# showroom_v1_schematic.net
KiCad netlist of a schematic drawn in Altium Designer
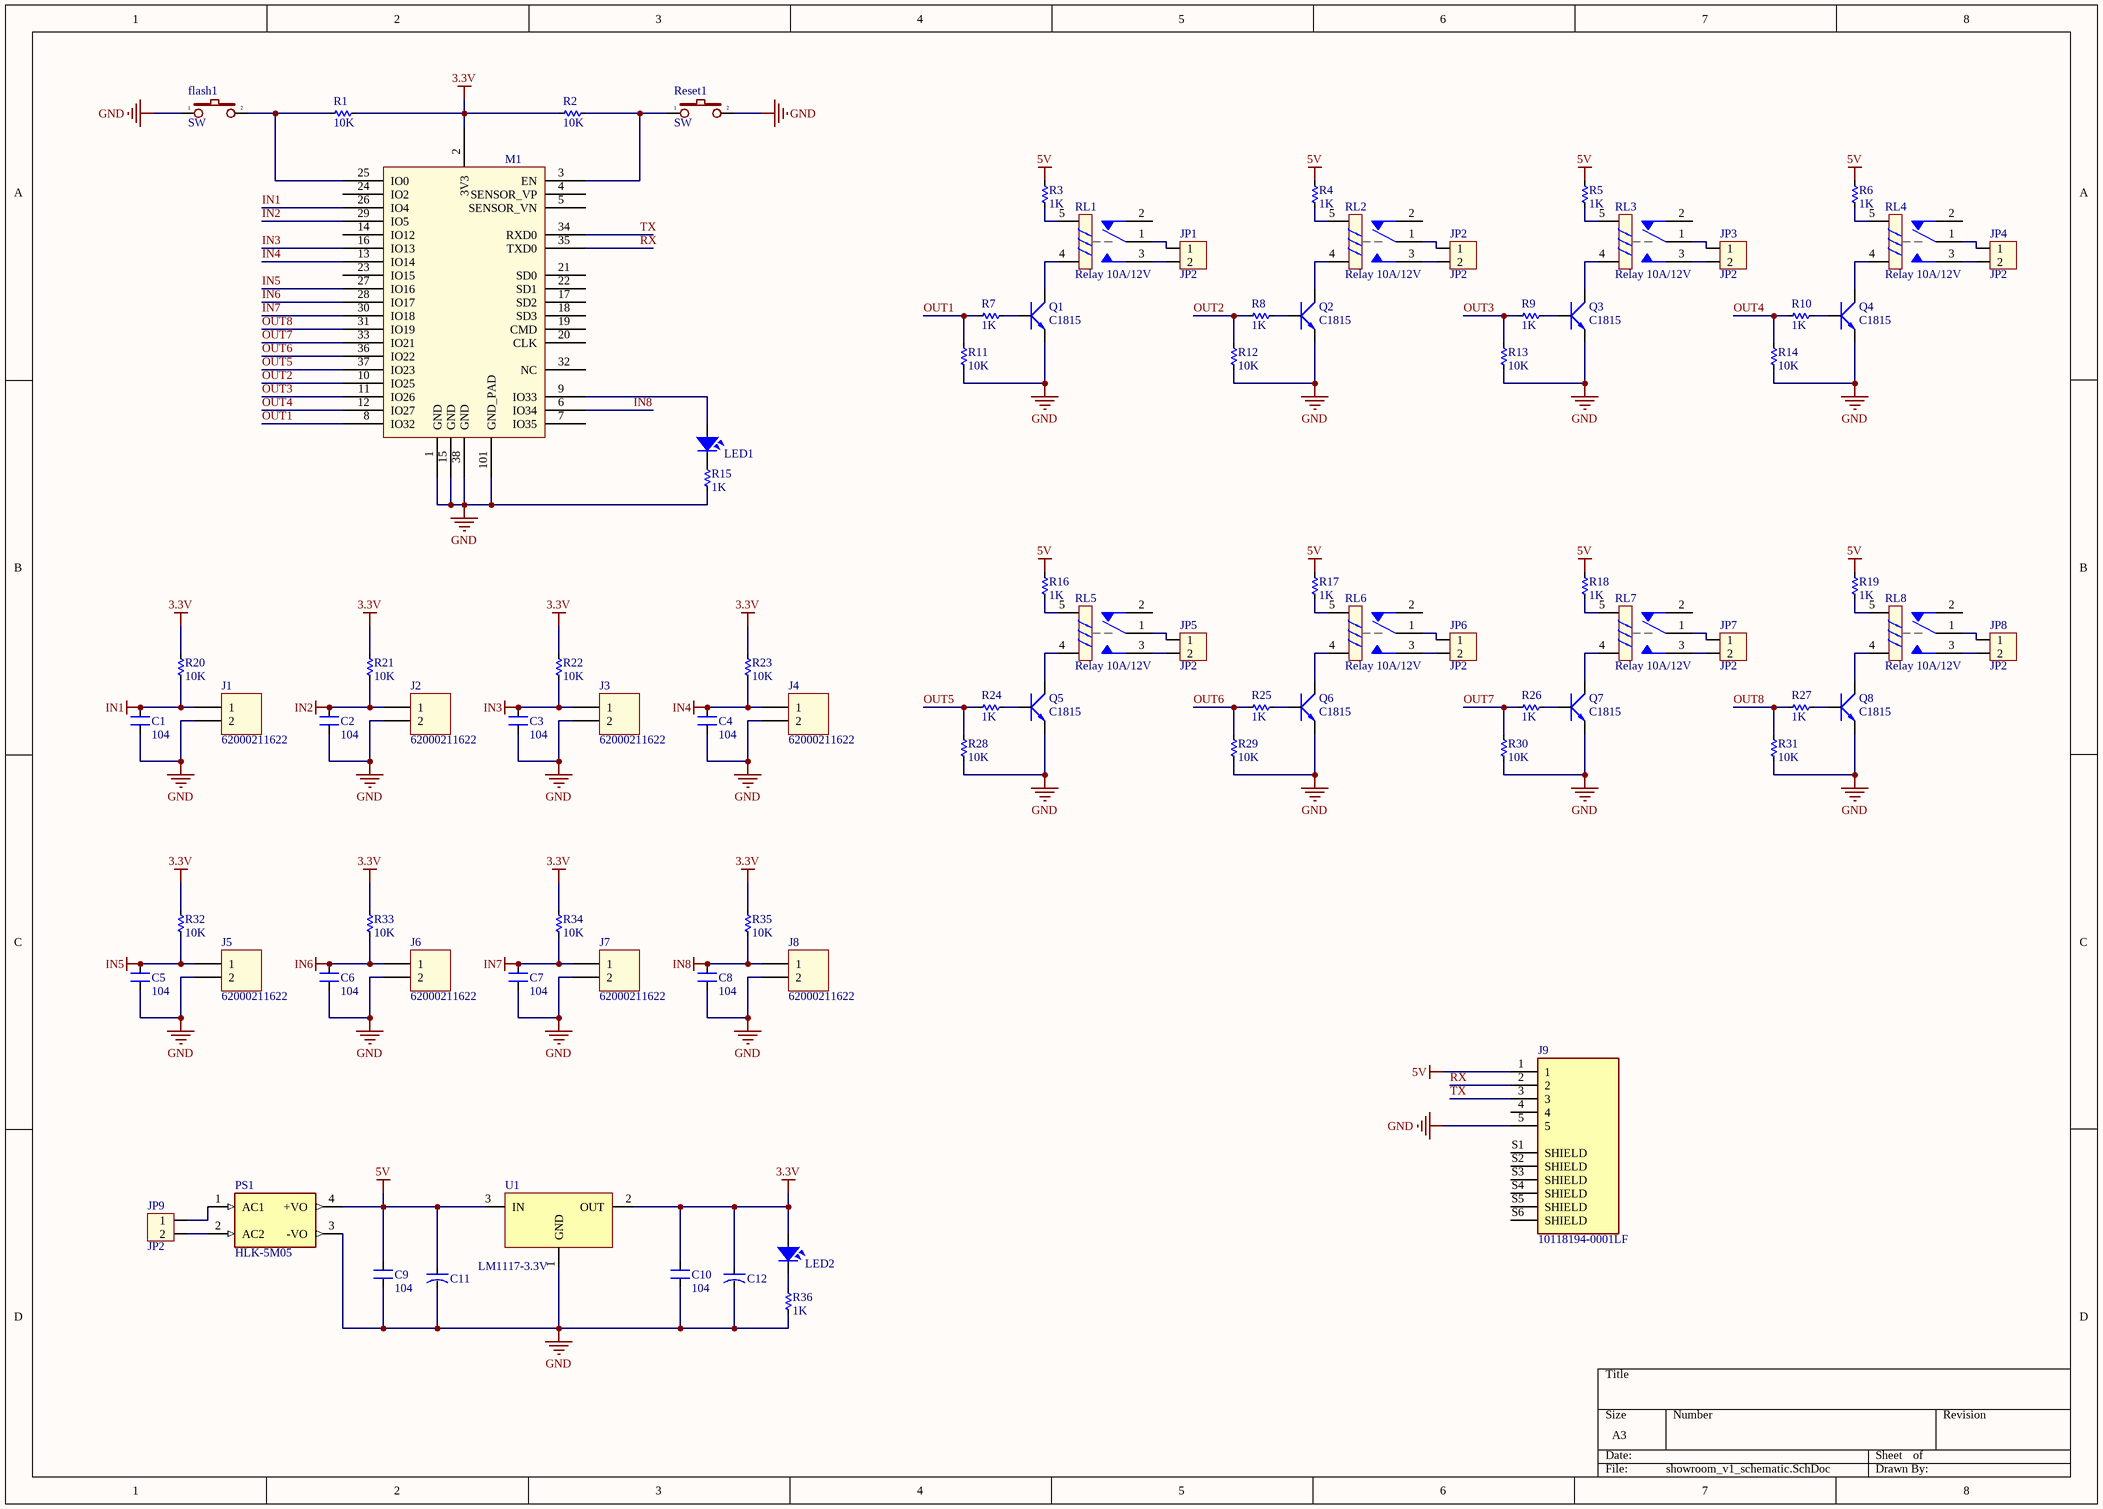
[diagram p0: showroom_v1_schematic.SchDoc]

(export (version "E")
  (design (tool "Eeschema 10.0.6"))
  (components
    (comp (ref "C1")
      (value "104")
      (footprint "SM-CAP-0805")
      (fields (field (name "DESIGNED BY") "VanDungEvn"))
      (libsource (lib "electronicvn-library1") (part "CN"))
    )
    (comp (ref "C2")
      (value "104")
      (footprint "SM-CAP-0805")
      (fields (field (name "DESIGNED BY") "VanDungEvn"))
      (libsource (lib "electronicvn-library1") (part "CN"))
    )
    (comp (ref "C3")
      (value "104")
      (footprint "SM-CAP-0805")
      (fields (field (name "DESIGNED BY") "VanDungEvn"))
      (libsource (lib "electronicvn-library1") (part "CN"))
    )
    (comp (ref "C4")
      (value "104")
      (footprint "SM-CAP-0805")
      (fields (field (name "DESIGNED BY") "VanDungEvn"))
      (libsource (lib "electronicvn-library1") (part "CN"))
    )
    (comp (ref "C5")
      (value "104")
      (footprint "SM-CAP-0805")
      (fields (field (name "DESIGNED BY") "VanDungEvn"))
      (libsource (lib "electronicvn-library1") (part "CN"))
    )
    (comp (ref "C6")
      (value "104")
      (footprint "SM-CAP-0805")
      (fields (field (name "DESIGNED BY") "VanDungEvn"))
      (libsource (lib "electronicvn-library1") (part "CN"))
    )
    (comp (ref "C7")
      (value "104")
      (footprint "SM-CAP-0805")
      (fields (field (name "DESIGNED BY") "VanDungEvn"))
      (libsource (lib "electronicvn-library1") (part "CN"))
    )
    (comp (ref "C8")
      (value "104")
      (footprint "SM-CAP-0805")
      (fields (field (name "DESIGNED BY") "VanDungEvn"))
      (libsource (lib "electronicvn-library1") (part "CN"))
    )
    (comp (ref "C9")
      (value "104")
      (footprint "SM-CAP-0805")
      (fields (field (name "DESIGNED BY") "VanDungEvn"))
      (libsource (lib "electronicvn-library1") (part "CN"))
    )
    (comp (ref "C10")
      (value "104")
      (footprint "SM-CAP-0805")
      (fields (field (name "DESIGNED BY") "VanDungEvn"))
      (libsource (lib "electronicvn-library1") (part "CN"))
    )
    (comp (ref "C11")
      (value "CN-ALU-SMD")
      (footprint "CAP-ALU-SMD-4.5x5x1.4")
      (description "Polarized Capacitor (Axial)")
      (fields (field (name "PUBLISHER") "Altium Limited"))
      (libsource (lib "LIBTanCN") (part "CN-ALU-SMD"))
    )
    (comp (ref "C12")
      (value "CN-ALU-SMD")
      (footprint "CAP-ALU-SMD-4.5x5x1.4")
      (description "Polarized Capacitor (Axial)")
      (fields (field (name "PUBLISHER") "Altium Limited"))
      (libsource (lib "LIBTanCN") (part "CN-ALU-SMD"))
    )
    (comp (ref "flash1")
      (value "SW")
      (footprint "SW-DIP1")
      (description "Switch button 2 pin")
      (libsource (lib "LIBRARY") (part "SW2"))
    )
    (comp (ref "J1")
      (value "62000211622")
      (footprint "62000211622")
      (description "WR-WTB 2.00mm Male Vertical Shrouded Header, 2p")
      (fields (field (name "PUBLISHER") "Wurth Elektronik"))
      (libsource (lib "Header2.0") (part "62000211622"))
    )
    (comp (ref "J2")
      (value "62000211622")
      (footprint "62000211622")
      (description "WR-WTB 2.00mm Male Vertical Shrouded Header, 2p")
      (fields (field (name "PUBLISHER") "Wurth Elektronik"))
      (libsource (lib "Header2.0") (part "62000211622"))
    )
    (comp (ref "J3")
      (value "62000211622")
      (footprint "62000211622")
      (description "WR-WTB 2.00mm Male Vertical Shrouded Header, 2p")
      (fields (field (name "PUBLISHER") "Wurth Elektronik"))
      (libsource (lib "Header2.0") (part "62000211622"))
    )
    (comp (ref "J4")
      (value "62000211622")
      (footprint "62000211622")
      (description "WR-WTB 2.00mm Male Vertical Shrouded Header, 2p")
      (fields (field (name "PUBLISHER") "Wurth Elektronik"))
      (libsource (lib "Header2.0") (part "62000211622"))
    )
    (comp (ref "J5")
      (value "62000211622")
      (footprint "62000211622")
      (description "WR-WTB 2.00mm Male Vertical Shrouded Header, 2p")
      (fields (field (name "PUBLISHER") "Wurth Elektronik"))
      (libsource (lib "Header2.0") (part "62000211622"))
    )
    (comp (ref "J6")
      (value "62000211622")
      (footprint "62000211622")
      (description "WR-WTB 2.00mm Male Vertical Shrouded Header, 2p")
      (fields (field (name "PUBLISHER") "Wurth Elektronik"))
      (libsource (lib "Header2.0") (part "62000211622"))
    )
    (comp (ref "J7")
      (value "62000211622")
      (footprint "62000211622")
      (description "WR-WTB 2.00mm Male Vertical Shrouded Header, 2p")
      (fields (field (name "PUBLISHER") "Wurth Elektronik"))
      (libsource (lib "Header2.0") (part "62000211622"))
    )
    (comp (ref "J8")
      (value "62000211622")
      (footprint "62000211622")
      (description "WR-WTB 2.00mm Male Vertical Shrouded Header, 2p")
      (fields (field (name "PUBLISHER") "Wurth Elektronik"))
      (libsource (lib "Header2.0") (part "62000211622"))
    )
    (comp (ref "J9")
      (value "10118194-0001LF")
      (footprint "AMPHENOL_10118194-0001LF")
      (description "USB - micro B USB 2.0 Receptacle Connector 5 Position Surface Mount, Right Angle; Through Hole")
      (fields (field (name "MF") "Amphenol ICC"))
      (libsource (lib "10118194-0001LF") (part "10118194-0001LF"))
    )
    (comp (ref "JP1")
      (value "JP2")
      (footprint "CON 2/7.62mm")
      (description "Connector 2")
      (libsource (lib "") (part "Con2_1"))
    )
    (comp (ref "JP2")
      (value "JP2")
      (footprint "CON 2/7.62mm")
      (description "Connector 2")
      (libsource (lib "") (part "Con2_1"))
    )
    (comp (ref "JP3")
      (value "JP2")
      (footprint "CON 2/7.62mm")
      (description "Connector 2")
      (libsource (lib "") (part "Con2_1"))
    )
    (comp (ref "JP4")
      (value "JP2")
      (footprint "CON 2/7.62mm")
      (description "Connector 2")
      (libsource (lib "") (part "Con2_1"))
    )
    (comp (ref "JP5")
      (value "JP2")
      (footprint "CON 2/7.62mm")
      (description "Connector 2")
      (libsource (lib "") (part "Con2_1"))
    )
    (comp (ref "JP6")
      (value "JP2")
      (footprint "CON 2/7.62mm")
      (description "Connector 2")
      (libsource (lib "") (part "Con2_1"))
    )
    (comp (ref "JP7")
      (value "JP2")
      (footprint "CON 2/7.62mm")
      (description "Connector 2")
      (libsource (lib "") (part "Con2_1"))
    )
    (comp (ref "JP8")
      (value "JP2")
      (footprint "CON 2/7.62mm")
      (description "Connector 2")
      (libsource (lib "") (part "Con2_1"))
    )
    (comp (ref "JP9")
      (value "JP2")
      (footprint "CON 2/7.62mm")
      (description "Connector 2")
      (libsource (lib "Tr.Thoai") (part "Con2"))
    )
    (comp (ref "LED1") (value "LED") (footprint "LED-0805-Blue") (libsource (lib "LIBRARY") (part "LED SMD")))
    (comp (ref "LED2") (value "LED") (footprint "LED-0805-Blue") (libsource (lib "LIBRARY") (part "LED SMD")))
    (comp (ref "M1")
      (value "ESP32S_Module")
      (footprint "ESP32S")
      (description "Esp-32S")
      (libsource (lib "ESP32S") (part "ESP32S_Module"))
    )
    (comp (ref "PS1")
      (value "HLK-5M05")
      (footprint "CONV_HLK-5M05")
      (description "AC DC 220V to 5V 5W 5Watt Isolated Switching Step-Down Power Supply Module Converter")
      (fields (field (name "MF") "Hi-link"))
      (libsource (lib "HLK-5M05") (part "HLK-5M05"))
    )
    (comp (ref "Q1")
      (value "C1815")
      (footprint "SOT23B")
      (description "NPN 600mW, ECB")
      (libsource (lib "electronicvn-library1") (part "C1815"))
    )
    (comp (ref "Q2")
      (value "C1815")
      (footprint "SOT23B")
      (description "NPN 600mW, ECB")
      (libsource (lib "electronicvn-library1") (part "C1815"))
    )
    (comp (ref "Q3")
      (value "C1815")
      (footprint "SOT23B")
      (description "NPN 600mW, ECB")
      (libsource (lib "electronicvn-library1") (part "C1815"))
    )
    (comp (ref "Q4")
      (value "C1815")
      (footprint "SOT23B")
      (description "NPN 600mW, ECB")
      (libsource (lib "electronicvn-library1") (part "C1815"))
    )
    (comp (ref "Q5")
      (value "C1815")
      (footprint "SOT23B")
      (description "NPN 600mW, ECB")
      (libsource (lib "electronicvn-library1") (part "C1815"))
    )
    (comp (ref "Q6")
      (value "C1815")
      (footprint "SOT23B")
      (description "NPN 600mW, ECB")
      (libsource (lib "electronicvn-library1") (part "C1815"))
    )
    (comp (ref "Q7")
      (value "C1815")
      (footprint "SOT23B")
      (description "NPN 600mW, ECB")
      (libsource (lib "electronicvn-library1") (part "C1815"))
    )
    (comp (ref "Q8")
      (value "C1815")
      (footprint "SOT23B")
      (description "NPN 600mW, ECB")
      (libsource (lib "electronicvn-library1") (part "C1815"))
    )
    (comp (ref "R1")
      (value "10K")
      (footprint "RES-SMD-0805")
      (description "Resistor")
      (fields
        (field (name "MANUFACTURER") "Generic Components")
        (field (name "PUBLISHER") "Altium Hobart Technology Centre")
      )
      (libsource (lib "LIBRARY") (part "Res-SMD"))
    )
    (comp (ref "R2")
      (value "10K")
      (footprint "RES-SMD-0805")
      (description "Resistor")
      (fields
        (field (name "MANUFACTURER") "Generic Components")
        (field (name "PUBLISHER") "Altium Hobart Technology Centre")
      )
      (libsource (lib "LIBRARY") (part "Res-SMD"))
    )
    (comp (ref "R3")
      (value "1K")
      (footprint "RES-SMD-0805")
      (description "Resistor")
      (fields
        (field (name "MANUFACTURER") "Generic Components")
        (field (name "PUBLISHER") "Altium Hobart Technology Centre")
      )
      (libsource (lib "LIBRARY") (part "Res-SMD"))
    )
    (comp (ref "R4")
      (value "1K")
      (footprint "RES-SMD-0805")
      (description "Resistor")
      (fields
        (field (name "MANUFACTURER") "Generic Components")
        (field (name "PUBLISHER") "Altium Hobart Technology Centre")
      )
      (libsource (lib "LIBRARY") (part "Res-SMD"))
    )
    (comp (ref "R5")
      (value "1K")
      (footprint "RES-SMD-0805")
      (description "Resistor")
      (fields
        (field (name "MANUFACTURER") "Generic Components")
        (field (name "PUBLISHER") "Altium Hobart Technology Centre")
      )
      (libsource (lib "LIBRARY") (part "Res-SMD"))
    )
    (comp (ref "R6")
      (value "1K")
      (footprint "RES-SMD-0805")
      (description "Resistor")
      (fields
        (field (name "MANUFACTURER") "Generic Components")
        (field (name "PUBLISHER") "Altium Hobart Technology Centre")
      )
      (libsource (lib "LIBRARY") (part "Res-SMD"))
    )
    (comp (ref "R7")
      (value "1K")
      (footprint "RES-SMD-0805")
      (description "Resistor")
      (fields
        (field (name "MANUFACTURER") "Generic Components")
        (field (name "PUBLISHER") "Altium Hobart Technology Centre")
      )
      (libsource (lib "LIBRARY") (part "Res-SMD"))
    )
    (comp (ref "R8")
      (value "1K")
      (footprint "RES-SMD-0805")
      (description "Resistor")
      (fields
        (field (name "MANUFACTURER") "Generic Components")
        (field (name "PUBLISHER") "Altium Hobart Technology Centre")
      )
      (libsource (lib "LIBRARY") (part "Res-SMD"))
    )
    (comp (ref "R9")
      (value "1K")
      (footprint "RES-SMD-0805")
      (description "Resistor")
      (fields
        (field (name "MANUFACTURER") "Generic Components")
        (field (name "PUBLISHER") "Altium Hobart Technology Centre")
      )
      (libsource (lib "LIBRARY") (part "Res-SMD"))
    )
    (comp (ref "R10")
      (value "1K")
      (footprint "RES-SMD-0805")
      (description "Resistor")
      (fields
        (field (name "MANUFACTURER") "Generic Components")
        (field (name "PUBLISHER") "Altium Hobart Technology Centre")
      )
      (libsource (lib "LIBRARY") (part "Res-SMD"))
    )
    (comp (ref "R11")
      (value "10K")
      (footprint "RES-SMD-0805")
      (description "Resistor")
      (fields
        (field (name "MANUFACTURER") "Generic Components")
        (field (name "PUBLISHER") "Altium Hobart Technology Centre")
      )
      (libsource (lib "LIBRARY") (part "Res-SMD"))
    )
    (comp (ref "R12")
      (value "10K")
      (footprint "RES-SMD-0805")
      (description "Resistor")
      (fields
        (field (name "MANUFACTURER") "Generic Components")
        (field (name "PUBLISHER") "Altium Hobart Technology Centre")
      )
      (libsource (lib "LIBRARY") (part "Res-SMD"))
    )
    (comp (ref "R13")
      (value "10K")
      (footprint "RES-SMD-0805")
      (description "Resistor")
      (fields
        (field (name "MANUFACTURER") "Generic Components")
        (field (name "PUBLISHER") "Altium Hobart Technology Centre")
      )
      (libsource (lib "LIBRARY") (part "Res-SMD"))
    )
    (comp (ref "R14")
      (value "10K")
      (footprint "RES-SMD-0805")
      (description "Resistor")
      (fields
        (field (name "MANUFACTURER") "Generic Components")
        (field (name "PUBLISHER") "Altium Hobart Technology Centre")
      )
      (libsource (lib "LIBRARY") (part "Res-SMD"))
    )
    (comp (ref "R15")
      (value "1K")
      (footprint "RES-SMD-0805")
      (description "Resistor")
      (fields
        (field (name "MANUFACTURER") "Generic Components")
        (field (name "PUBLISHER") "Altium Hobart Technology Centre")
      )
      (libsource (lib "LIBRARY") (part "Res-SMD"))
    )
    (comp (ref "R16")
      (value "1K")
      (footprint "RES-SMD-0805")
      (description "Resistor")
      (fields
        (field (name "MANUFACTURER") "Generic Components")
        (field (name "PUBLISHER") "Altium Hobart Technology Centre")
      )
      (libsource (lib "LIBRARY") (part "Res-SMD"))
    )
    (comp (ref "R17")
      (value "1K")
      (footprint "RES-SMD-0805")
      (description "Resistor")
      (fields
        (field (name "MANUFACTURER") "Generic Components")
        (field (name "PUBLISHER") "Altium Hobart Technology Centre")
      )
      (libsource (lib "LIBRARY") (part "Res-SMD"))
    )
    (comp (ref "R18")
      (value "1K")
      (footprint "RES-SMD-0805")
      (description "Resistor")
      (fields
        (field (name "MANUFACTURER") "Generic Components")
        (field (name "PUBLISHER") "Altium Hobart Technology Centre")
      )
      (libsource (lib "LIBRARY") (part "Res-SMD"))
    )
    (comp (ref "R19")
      (value "1K")
      (footprint "RES-SMD-0805")
      (description "Resistor")
      (fields
        (field (name "MANUFACTURER") "Generic Components")
        (field (name "PUBLISHER") "Altium Hobart Technology Centre")
      )
      (libsource (lib "LIBRARY") (part "Res-SMD"))
    )
    (comp (ref "R20")
      (value "10K")
      (footprint "RES-SMD-0805")
      (description "Resistor")
      (fields
        (field (name "MANUFACTURER") "Generic Components")
        (field (name "PUBLISHER") "Altium Hobart Technology Centre")
      )
      (libsource (lib "LIBRARY") (part "Res-SMD"))
    )
    (comp (ref "R21")
      (value "10K")
      (footprint "RES-SMD-0805")
      (description "Resistor")
      (fields
        (field (name "MANUFACTURER") "Generic Components")
        (field (name "PUBLISHER") "Altium Hobart Technology Centre")
      )
      (libsource (lib "LIBRARY") (part "Res-SMD"))
    )
    (comp (ref "R22")
      (value "10K")
      (footprint "RES-SMD-0805")
      (description "Resistor")
      (fields
        (field (name "MANUFACTURER") "Generic Components")
        (field (name "PUBLISHER") "Altium Hobart Technology Centre")
      )
      (libsource (lib "LIBRARY") (part "Res-SMD"))
    )
    (comp (ref "R23")
      (value "10K")
      (footprint "RES-SMD-0805")
      (description "Resistor")
      (fields
        (field (name "MANUFACTURER") "Generic Components")
        (field (name "PUBLISHER") "Altium Hobart Technology Centre")
      )
      (libsource (lib "LIBRARY") (part "Res-SMD"))
    )
    (comp (ref "R24")
      (value "1K")
      (footprint "RES-SMD-0805")
      (description "Resistor")
      (fields
        (field (name "MANUFACTURER") "Generic Components")
        (field (name "PUBLISHER") "Altium Hobart Technology Centre")
      )
      (libsource (lib "LIBRARY") (part "Res-SMD"))
    )
    (comp (ref "R25")
      (value "1K")
      (footprint "RES-SMD-0805")
      (description "Resistor")
      (fields
        (field (name "MANUFACTURER") "Generic Components")
        (field (name "PUBLISHER") "Altium Hobart Technology Centre")
      )
      (libsource (lib "LIBRARY") (part "Res-SMD"))
    )
    (comp (ref "R26")
      (value "1K")
      (footprint "RES-SMD-0805")
      (description "Resistor")
      (fields
        (field (name "MANUFACTURER") "Generic Components")
        (field (name "PUBLISHER") "Altium Hobart Technology Centre")
      )
      (libsource (lib "LIBRARY") (part "Res-SMD"))
    )
    (comp (ref "R27")
      (value "1K")
      (footprint "RES-SMD-0805")
      (description "Resistor")
      (fields
        (field (name "MANUFACTURER") "Generic Components")
        (field (name "PUBLISHER") "Altium Hobart Technology Centre")
      )
      (libsource (lib "LIBRARY") (part "Res-SMD"))
    )
    (comp (ref "R28")
      (value "10K")
      (footprint "RES-SMD-0805")
      (description "Resistor")
      (fields
        (field (name "MANUFACTURER") "Generic Components")
        (field (name "PUBLISHER") "Altium Hobart Technology Centre")
      )
      (libsource (lib "LIBRARY") (part "Res-SMD"))
    )
    (comp (ref "R29")
      (value "10K")
      (footprint "RES-SMD-0805")
      (description "Resistor")
      (fields
        (field (name "MANUFACTURER") "Generic Components")
        (field (name "PUBLISHER") "Altium Hobart Technology Centre")
      )
      (libsource (lib "LIBRARY") (part "Res-SMD"))
    )
    (comp (ref "R30")
      (value "10K")
      (footprint "RES-SMD-0805")
      (description "Resistor")
      (fields
        (field (name "MANUFACTURER") "Generic Components")
        (field (name "PUBLISHER") "Altium Hobart Technology Centre")
      )
      (libsource (lib "LIBRARY") (part "Res-SMD"))
    )
    (comp (ref "R31")
      (value "10K")
      (footprint "RES-SMD-0805")
      (description "Resistor")
      (fields
        (field (name "MANUFACTURER") "Generic Components")
        (field (name "PUBLISHER") "Altium Hobart Technology Centre")
      )
      (libsource (lib "LIBRARY") (part "Res-SMD"))
    )
    (comp (ref "R32")
      (value "10K")
      (footprint "RES-SMD-0805")
      (description "Resistor")
      (fields
        (field (name "MANUFACTURER") "Generic Components")
        (field (name "PUBLISHER") "Altium Hobart Technology Centre")
      )
      (libsource (lib "LIBRARY") (part "Res-SMD"))
    )
    (comp (ref "R33")
      (value "10K")
      (footprint "RES-SMD-0805")
      (description "Resistor")
      (fields
        (field (name "MANUFACTURER") "Generic Components")
        (field (name "PUBLISHER") "Altium Hobart Technology Centre")
      )
      (libsource (lib "LIBRARY") (part "Res-SMD"))
    )
    (comp (ref "R34")
      (value "10K")
      (footprint "RES-SMD-0805")
      (description "Resistor")
      (fields
        (field (name "MANUFACTURER") "Generic Components")
        (field (name "PUBLISHER") "Altium Hobart Technology Centre")
      )
      (libsource (lib "LIBRARY") (part "Res-SMD"))
    )
    (comp (ref "R35")
      (value "10K")
      (footprint "RES-SMD-0805")
      (description "Resistor")
      (fields
        (field (name "MANUFACTURER") "Generic Components")
        (field (name "PUBLISHER") "Altium Hobart Technology Centre")
      )
      (libsource (lib "LIBRARY") (part "Res-SMD"))
    )
    (comp (ref "R36")
      (value "1K")
      (footprint "RES-SMD-0805")
      (description "Resistor")
      (fields
        (field (name "MANUFACTURER") "Generic Components")
        (field (name "PUBLISHER") "Altium Hobart Technology Centre")
      )
      (libsource (lib "LIBRARY") (part "Res-SMD"))
    )
    (comp (ref "Reset1")
      (value "SW")
      (footprint "SW1-SMD")
      (description "Switch button 2 pin")
      (libsource (lib "LIBRARY") (part "SW2"))
    )
    (comp (ref "RL1")
      (value "Relay 10A/12V")
      (footprint "RELAY 5")
      (description "Relay SPDT,10A - 12VDC 5 Pin")
      (libsource (lib "LIBRARY") (part "Relay 5"))
    )
    (comp (ref "RL2")
      (value "Relay 10A/12V")
      (footprint "RELAY 5")
      (description "Relay SPDT,10A - 12VDC 5 Pin")
      (libsource (lib "LIBRARY") (part "Relay 5"))
    )
    (comp (ref "RL3")
      (value "Relay 10A/12V")
      (footprint "RELAY 5")
      (description "Relay SPDT,10A - 12VDC 5 Pin")
      (libsource (lib "LIBRARY") (part "Relay 5"))
    )
    (comp (ref "RL4")
      (value "Relay 10A/12V")
      (footprint "RELAY 5")
      (description "Relay SPDT,10A - 12VDC 5 Pin")
      (libsource (lib "LIBRARY") (part "Relay 5"))
    )
    (comp (ref "RL5")
      (value "Relay 10A/12V")
      (footprint "RELAY 5")
      (description "Relay SPDT,10A - 12VDC 5 Pin")
      (libsource (lib "LIBRARY") (part "Relay 5"))
    )
    (comp (ref "RL6")
      (value "Relay 10A/12V")
      (footprint "RELAY 5")
      (description "Relay SPDT,10A - 12VDC 5 Pin")
      (libsource (lib "LIBRARY") (part "Relay 5"))
    )
    (comp (ref "RL7")
      (value "Relay 10A/12V")
      (footprint "RELAY 5")
      (description "Relay SPDT,10A - 12VDC 5 Pin")
      (libsource (lib "LIBRARY") (part "Relay 5"))
    )
    (comp (ref "RL8")
      (value "Relay 10A/12V")
      (footprint "RELAY 5")
      (description "Relay SPDT,10A - 12VDC 5 Pin")
      (libsource (lib "LIBRARY") (part "Relay 5"))
    )
    (comp (ref "U1")
      (value "LM1117-3.3V")
      (footprint "SOT223")
      (description "800mA Low-Dropout Linear Regulator")
      (fields (field (name "CREATOR") "Nguyen Ba Bien"))
      (libsource (lib "LIBRARY") (part "LM1117"))
    )
  )
  (nets
    (net (code "1") (name "/OUT1") (class "Default")
      (node (ref "M1") (pin "8") (pinfunction "IO32_8") (pintype "passive"))
      (node (ref "R11") (pin "2") (pinfunction "2_2") (pintype "passive"))
      (node (ref "R7") (pin "1") (pinfunction "1_1") (pintype "passive"))
    )
    (net (code "2") (name "/OUT2") (class "Default")
      (node (ref "M1") (pin "10") (pinfunction "IO25_10") (pintype "passive"))
      (node (ref "R12") (pin "2") (pinfunction "2_2") (pintype "passive"))
      (node (ref "R8") (pin "1") (pinfunction "1_1") (pintype "passive"))
    )
    (net (code "3") (name "/OUT3") (class "Default")
      (node (ref "M1") (pin "11") (pinfunction "IO26_11") (pintype "passive"))
      (node (ref "R13") (pin "2") (pinfunction "2_2") (pintype "passive"))
      (node (ref "R9") (pin "1") (pinfunction "1_1") (pintype "passive"))
    )
    (net (code "4") (name "/OUT4") (class "Default")
      (node (ref "M1") (pin "12") (pinfunction "IO27_12") (pintype "passive"))
      (node (ref "R10") (pin "1") (pinfunction "1_1") (pintype "passive"))
      (node (ref "R14") (pin "2") (pinfunction "2_2") (pintype "passive"))
    )
    (net (code "5") (name "/OUT5") (class "Default")
      (node (ref "M1") (pin "37") (pinfunction "IO23_37") (pintype "passive"))
      (node (ref "R24") (pin "1") (pinfunction "1_1") (pintype "passive"))
      (node (ref "R28") (pin "2") (pinfunction "2_2") (pintype "passive"))
    )
    (net (code "6") (name "/OUT6") (class "Default")
      (node (ref "M1") (pin "36") (pinfunction "IO22_36") (pintype "passive"))
      (node (ref "R25") (pin "1") (pinfunction "1_1") (pintype "passive"))
      (node (ref "R29") (pin "2") (pinfunction "2_2") (pintype "passive"))
    )
    (net (code "7") (name "/OUT7") (class "Default")
      (node (ref "M1") (pin "33") (pinfunction "IO21_33") (pintype "passive"))
      (node (ref "R26") (pin "1") (pinfunction "1_1") (pintype "passive"))
      (node (ref "R30") (pin "2") (pinfunction "2_2") (pintype "passive"))
    )
    (net (code "8") (name "/OUT8") (class "Default")
      (node (ref "M1") (pin "31") (pinfunction "IO19_31") (pintype "passive"))
      (node (ref "R27") (pin "1") (pinfunction "1_1") (pintype "passive"))
      (node (ref "R31") (pin "2") (pinfunction "2_2") (pintype "passive"))
    )
    (net (code "9") (name "/RX") (class "Default")
      (node (ref "J9") (pin "2") (pinfunction "2_2") (pintype "passive"))
      (node (ref "M1") (pin "35") (pinfunction "TXD0_35") (pintype "passive"))
    )
    (net (code "10") (name "/TX") (class "Default")
      (node (ref "J9") (pin "3") (pinfunction "3_3") (pintype "passive"))
      (node (ref "M1") (pin "34") (pinfunction "RXD0_34") (pintype "passive"))
    )
    (net (code "11") (name "3.3V") (class "Default")
      (node (ref "C10") (pin "2") (pinfunction "2_2") (pintype "passive"))
      (node (ref "C12") (pin "1") (pinfunction "1_1") (pintype "passive"))
      (node (ref "LED2") (pin "1") (pinfunction "1_1") (pintype "passive"))
      (node (ref "M1") (pin "2") (pinfunction "3V3_2") (pintype "power_in"))
      (node (ref "R1") (pin "2") (pinfunction "2_2") (pintype "passive"))
      (node (ref "R2") (pin "1") (pinfunction "1_1") (pintype "passive"))
      (node (ref "R20") (pin "2") (pinfunction "2_2") (pintype "passive"))
      (node (ref "R21") (pin "2") (pinfunction "2_2") (pintype "passive"))
      (node (ref "R22") (pin "2") (pinfunction "2_2") (pintype "passive"))
      (node (ref "R23") (pin "2") (pinfunction "2_2") (pintype "passive"))
      (node (ref "R32") (pin "2") (pinfunction "2_2") (pintype "passive"))
      (node (ref "R33") (pin "2") (pinfunction "2_2") (pintype "passive"))
      (node (ref "R34") (pin "2") (pinfunction "2_2") (pintype "passive"))
      (node (ref "R35") (pin "2") (pinfunction "2_2") (pintype "passive"))
      (node (ref "U1") (pin "2") (pinfunction "OUT_2") (pintype "passive"))
    )
    (net (code "12") (name "5V") (class "Default")
      (node (ref "C11") (pin "1") (pinfunction "1_1") (pintype "passive"))
      (node (ref "C9") (pin "2") (pinfunction "2_2") (pintype "passive"))
      (node (ref "J9") (pin "1") (pinfunction "1_1") (pintype "passive"))
      (node (ref "PS1") (pin "4") (pinfunction "+VO_4") (pintype "output"))
      (node (ref "R16") (pin "2") (pinfunction "2_2") (pintype "passive"))
      (node (ref "R17") (pin "2") (pinfunction "2_2") (pintype "passive"))
      (node (ref "R18") (pin "2") (pinfunction "2_2") (pintype "passive"))
      (node (ref "R19") (pin "2") (pinfunction "2_2") (pintype "passive"))
      (node (ref "R3") (pin "2") (pinfunction "2_2") (pintype "passive"))
      (node (ref "R4") (pin "2") (pinfunction "2_2") (pintype "passive"))
      (node (ref "R5") (pin "2") (pinfunction "2_2") (pintype "passive"))
      (node (ref "R6") (pin "2") (pinfunction "2_2") (pintype "passive"))
      (node (ref "U1") (pin "3") (pinfunction "IN_3") (pintype "passive"))
    )
    (net (code "13") (name "GND") (class "Default")
      (node (ref "C1") (pin "1") (pinfunction "1_1") (pintype "passive"))
      (node (ref "C10") (pin "1") (pinfunction "1_1") (pintype "passive"))
      (node (ref "C11") (pin "2") (pinfunction "2_2") (pintype "passive"))
      (node (ref "C12") (pin "2") (pinfunction "2_2") (pintype "passive"))
      (node (ref "C2") (pin "1") (pinfunction "1_1") (pintype "passive"))
      (node (ref "C3") (pin "1") (pinfunction "1_1") (pintype "passive"))
      (node (ref "C4") (pin "1") (pinfunction "1_1") (pintype "passive"))
      (node (ref "C5") (pin "1") (pinfunction "1_1") (pintype "passive"))
      (node (ref "C6") (pin "1") (pinfunction "1_1") (pintype "passive"))
      (node (ref "C7") (pin "1") (pinfunction "1_1") (pintype "passive"))
      (node (ref "C8") (pin "1") (pinfunction "1_1") (pintype "passive"))
      (node (ref "C9") (pin "1") (pinfunction "1_1") (pintype "passive"))
      (node (ref "J1") (pin "2") (pinfunction "2_2") (pintype "passive"))
      (node (ref "J2") (pin "2") (pinfunction "2_2") (pintype "passive"))
      (node (ref "J3") (pin "2") (pinfunction "2_2") (pintype "passive"))
      (node (ref "J4") (pin "2") (pinfunction "2_2") (pintype "passive"))
      (node (ref "J5") (pin "2") (pinfunction "2_2") (pintype "passive"))
      (node (ref "J6") (pin "2") (pinfunction "2_2") (pintype "passive"))
      (node (ref "J7") (pin "2") (pinfunction "2_2") (pintype "passive"))
      (node (ref "J8") (pin "2") (pinfunction "2_2") (pintype "passive"))
      (node (ref "J9") (pin "5") (pinfunction "5_5") (pintype "passive"))
      (node (ref "M1") (pin "1") (pinfunction "GND_1") (pintype "power_in"))
      (node (ref "M1") (pin "101") (pinfunction "GND_PAD_101") (pintype "power_in"))
      (node (ref "M1") (pin "15") (pinfunction "GND_15") (pintype "power_in"))
      (node (ref "M1") (pin "38") (pinfunction "GND_38") (pintype "power_in"))
      (node (ref "PS1") (pin "3") (pinfunction "-VO_3") (pintype "output"))
      (node (ref "Q1") (pin "1") (pinfunction "E_1") (pintype "passive"))
      (node (ref "Q2") (pin "1") (pinfunction "E_1") (pintype "passive"))
      (node (ref "Q3") (pin "1") (pinfunction "E_1") (pintype "passive"))
      (node (ref "Q4") (pin "1") (pinfunction "E_1") (pintype "passive"))
      (node (ref "Q5") (pin "1") (pinfunction "E_1") (pintype "passive"))
      (node (ref "Q6") (pin "1") (pinfunction "E_1") (pintype "passive"))
      (node (ref "Q7") (pin "1") (pinfunction "E_1") (pintype "passive"))
      (node (ref "Q8") (pin "1") (pinfunction "E_1") (pintype "passive"))
      (node (ref "R11") (pin "1") (pinfunction "1_1") (pintype "passive"))
      (node (ref "R12") (pin "1") (pinfunction "1_1") (pintype "passive"))
      (node (ref "R13") (pin "1") (pinfunction "1_1") (pintype "passive"))
      (node (ref "R14") (pin "1") (pinfunction "1_1") (pintype "passive"))
      (node (ref "R15") (pin "1") (pinfunction "1_1") (pintype "passive"))
      (node (ref "R28") (pin "1") (pinfunction "1_1") (pintype "passive"))
      (node (ref "R29") (pin "1") (pinfunction "1_1") (pintype "passive"))
      (node (ref "R30") (pin "1") (pinfunction "1_1") (pintype "passive"))
      (node (ref "R31") (pin "1") (pinfunction "1_1") (pintype "passive"))
      (node (ref "R36") (pin "2") (pinfunction "2_2") (pintype "passive"))
      (node (ref "Reset1") (pin "2") (pinfunction "2_2") (pintype "passive"))
      (node (ref "U1") (pin "1") (pinfunction "GND_1") (pintype "passive"))
      (node (ref "flash1") (pin "1") (pinfunction "1_1") (pintype "passive"))
    )
    (net (code "14") (name "IN1") (class "Default")
      (node (ref "C1") (pin "2") (pinfunction "2_2") (pintype "passive"))
      (node (ref "J1") (pin "1") (pinfunction "1_1") (pintype "passive"))
      (node (ref "M1") (pin "26") (pinfunction "IO4_26") (pintype "passive"))
      (node (ref "R20") (pin "1") (pinfunction "1_1") (pintype "passive"))
    )
    (net (code "15") (name "IN2") (class "Default")
      (node (ref "C2") (pin "2") (pinfunction "2_2") (pintype "passive"))
      (node (ref "J2") (pin "1") (pinfunction "1_1") (pintype "passive"))
      (node (ref "M1") (pin "29") (pinfunction "IO5_29") (pintype "passive"))
      (node (ref "R21") (pin "1") (pinfunction "1_1") (pintype "passive"))
    )
    (net (code "16") (name "IN3") (class "Default")
      (node (ref "C3") (pin "2") (pinfunction "2_2") (pintype "passive"))
      (node (ref "J3") (pin "1") (pinfunction "1_1") (pintype "passive"))
      (node (ref "M1") (pin "16") (pinfunction "IO13_16") (pintype "passive"))
      (node (ref "R22") (pin "1") (pinfunction "1_1") (pintype "passive"))
    )
    (net (code "17") (name "IN4") (class "Default")
      (node (ref "C4") (pin "2") (pinfunction "2_2") (pintype "passive"))
      (node (ref "J4") (pin "1") (pinfunction "1_1") (pintype "passive"))
      (node (ref "M1") (pin "13") (pinfunction "IO14_13") (pintype "passive"))
      (node (ref "R23") (pin "1") (pinfunction "1_1") (pintype "passive"))
    )
    (net (code "18") (name "IN5") (class "Default")
      (node (ref "C5") (pin "2") (pinfunction "2_2") (pintype "passive"))
      (node (ref "J5") (pin "1") (pinfunction "1_1") (pintype "passive"))
      (node (ref "M1") (pin "27") (pinfunction "IO16_27") (pintype "passive"))
      (node (ref "R32") (pin "1") (pinfunction "1_1") (pintype "passive"))
    )
    (net (code "19") (name "IN6") (class "Default")
      (node (ref "C6") (pin "2") (pinfunction "2_2") (pintype "passive"))
      (node (ref "J6") (pin "1") (pinfunction "1_1") (pintype "passive"))
      (node (ref "M1") (pin "28") (pinfunction "IO17_28") (pintype "passive"))
      (node (ref "R33") (pin "1") (pinfunction "1_1") (pintype "passive"))
    )
    (net (code "20") (name "IN7") (class "Default")
      (node (ref "C7") (pin "2") (pinfunction "2_2") (pintype "passive"))
      (node (ref "J7") (pin "1") (pinfunction "1_1") (pintype "passive"))
      (node (ref "M1") (pin "30") (pinfunction "IO18_30") (pintype "passive"))
      (node (ref "R34") (pin "1") (pinfunction "1_1") (pintype "passive"))
    )
    (net (code "21") (name "IN8") (class "Default")
      (node (ref "C8") (pin "2") (pinfunction "2_2") (pintype "passive"))
      (node (ref "J8") (pin "1") (pinfunction "1_1") (pintype "passive"))
      (node (ref "M1") (pin "6") (pinfunction "IO34_6") (pintype "passive"))
      (node (ref "R35") (pin "1") (pinfunction "1_1") (pintype "passive"))
    )
    (net (code "22") (name "Net-(JP1-Pad1)") (class "Default")
      (node (ref "JP1") (pin "1") (pinfunction "1_1") (pintype "passive"))
      (node (ref "RL1") (pin "1") (pinfunction "1_1") (pintype "passive"))
    )
    (net (code "23") (name "Net-(JP1-Pad2)") (class "Default")
      (node (ref "JP1") (pin "2") (pinfunction "2_2") (pintype "passive"))
      (node (ref "RL1") (pin "3") (pinfunction "3_3") (pintype "passive"))
    )
    (net (code "24") (name "Net-(JP2-Pad1)") (class "Default")
      (node (ref "JP2") (pin "1") (pinfunction "1_1") (pintype "passive"))
      (node (ref "RL2") (pin "1") (pinfunction "1_1") (pintype "passive"))
    )
    (net (code "25") (name "Net-(JP2-Pad2)") (class "Default")
      (node (ref "JP2") (pin "2") (pinfunction "2_2") (pintype "passive"))
      (node (ref "RL2") (pin "3") (pinfunction "3_3") (pintype "passive"))
    )
    (net (code "26") (name "Net-(JP3-Pad1)") (class "Default")
      (node (ref "JP3") (pin "1") (pinfunction "1_1") (pintype "passive"))
      (node (ref "RL3") (pin "1") (pinfunction "1_1") (pintype "passive"))
    )
    (net (code "27") (name "Net-(JP3-Pad2)") (class "Default")
      (node (ref "JP3") (pin "2") (pinfunction "2_2") (pintype "passive"))
      (node (ref "RL3") (pin "3") (pinfunction "3_3") (pintype "passive"))
    )
    (net (code "28") (name "Net-(JP4-Pad1)") (class "Default")
      (node (ref "JP4") (pin "1") (pinfunction "1_1") (pintype "passive"))
      (node (ref "RL4") (pin "1") (pinfunction "1_1") (pintype "passive"))
    )
    (net (code "29") (name "Net-(JP4-Pad2)") (class "Default")
      (node (ref "JP4") (pin "2") (pinfunction "2_2") (pintype "passive"))
      (node (ref "RL4") (pin "3") (pinfunction "3_3") (pintype "passive"))
    )
    (net (code "30") (name "Net-(JP5-Pad1)") (class "Default")
      (node (ref "JP5") (pin "1") (pinfunction "1_1") (pintype "passive"))
      (node (ref "RL5") (pin "1") (pinfunction "1_1") (pintype "passive"))
    )
    (net (code "31") (name "Net-(JP5-Pad2)") (class "Default")
      (node (ref "JP5") (pin "2") (pinfunction "2_2") (pintype "passive"))
      (node (ref "RL5") (pin "3") (pinfunction "3_3") (pintype "passive"))
    )
    (net (code "32") (name "Net-(JP6-Pad1)") (class "Default")
      (node (ref "JP6") (pin "1") (pinfunction "1_1") (pintype "passive"))
      (node (ref "RL6") (pin "1") (pinfunction "1_1") (pintype "passive"))
    )
    (net (code "33") (name "Net-(JP6-Pad2)") (class "Default")
      (node (ref "JP6") (pin "2") (pinfunction "2_2") (pintype "passive"))
      (node (ref "RL6") (pin "3") (pinfunction "3_3") (pintype "passive"))
    )
    (net (code "34") (name "Net-(JP7-Pad1)") (class "Default")
      (node (ref "JP7") (pin "1") (pinfunction "1_1") (pintype "passive"))
      (node (ref "RL7") (pin "1") (pinfunction "1_1") (pintype "passive"))
    )
    (net (code "35") (name "Net-(JP7-Pad2)") (class "Default")
      (node (ref "JP7") (pin "2") (pinfunction "2_2") (pintype "passive"))
      (node (ref "RL7") (pin "3") (pinfunction "3_3") (pintype "passive"))
    )
    (net (code "36") (name "Net-(JP8-Pad1)") (class "Default")
      (node (ref "JP8") (pin "1") (pinfunction "1_1") (pintype "passive"))
      (node (ref "RL8") (pin "1") (pinfunction "1_1") (pintype "passive"))
    )
    (net (code "37") (name "Net-(JP8-Pad2)") (class "Default")
      (node (ref "JP8") (pin "2") (pinfunction "2_2") (pintype "passive"))
      (node (ref "RL8") (pin "3") (pinfunction "3_3") (pintype "passive"))
    )
    (net (code "38") (name "Net-(LED1-Pad2)") (class "Default")
      (node (ref "LED1") (pin "2") (pinfunction "2_2") (pintype "passive"))
      (node (ref "R15") (pin "2") (pinfunction "2_2") (pintype "passive"))
    )
    (net (code "39") (name "Net-(LED2-Pad2)") (class "Default")
      (node (ref "LED2") (pin "2") (pinfunction "2_2") (pintype "passive"))
      (node (ref "R36") (pin "1") (pinfunction "1_1") (pintype "passive"))
    )
    (net (code "40") (name "Net-(M1-EN)") (class "Default")
      (node (ref "M1") (pin "3") (pinfunction "EN_3") (pintype "power_in"))
      (node (ref "R2") (pin "2") (pinfunction "2_2") (pintype "passive"))
      (node (ref "Reset1") (pin "1") (pinfunction "1_1") (pintype "passive"))
    )
    (net (code "41") (name "Net-(M1-IO0)") (class "Default")
      (node (ref "M1") (pin "25") (pinfunction "IO0_25") (pintype "passive"))
      (node (ref "R1") (pin "1") (pinfunction "1_1") (pintype "passive"))
      (node (ref "flash1") (pin "2") (pinfunction "2_2") (pintype "passive"))
    )
    (net (code "42") (name "Net-(M1-IO33)") (class "Default")
      (node (ref "LED1") (pin "1") (pinfunction "1_1") (pintype "passive"))
      (node (ref "M1") (pin "9") (pinfunction "IO33_9") (pintype "passive"))
    )
    (net (code "43") (name "Net-(PS1-AC1)") (class "Default")
      (node (ref "JP9") (pin "1") (pinfunction "1_1") (pintype "passive"))
      (node (ref "PS1") (pin "1") (pinfunction "AC1_1") (pintype "input"))
    )
    (net (code "44") (name "Net-(PS1-AC2)") (class "Default")
      (node (ref "JP9") (pin "2") (pinfunction "2_2") (pintype "passive"))
      (node (ref "PS1") (pin "2") (pinfunction "AC2_2") (pintype "input"))
    )
    (net (code "45") (name "Net-(Q1-B)") (class "Default")
      (node (ref "Q1") (pin "3") (pinfunction "B_3") (pintype "passive"))
      (node (ref "R7") (pin "2") (pinfunction "2_2") (pintype "passive"))
    )
    (net (code "46") (name "Net-(Q1-C)") (class "Default")
      (node (ref "Q1") (pin "2") (pinfunction "C_2") (pintype "passive"))
      (node (ref "RL1") (pin "4") (pinfunction "4_4") (pintype "passive"))
    )
    (net (code "47") (name "Net-(Q2-B)") (class "Default")
      (node (ref "Q2") (pin "3") (pinfunction "B_3") (pintype "passive"))
      (node (ref "R8") (pin "2") (pinfunction "2_2") (pintype "passive"))
    )
    (net (code "48") (name "Net-(Q2-C)") (class "Default")
      (node (ref "Q2") (pin "2") (pinfunction "C_2") (pintype "passive"))
      (node (ref "RL2") (pin "4") (pinfunction "4_4") (pintype "passive"))
    )
    (net (code "49") (name "Net-(Q3-B)") (class "Default")
      (node (ref "Q3") (pin "3") (pinfunction "B_3") (pintype "passive"))
      (node (ref "R9") (pin "2") (pinfunction "2_2") (pintype "passive"))
    )
    (net (code "50") (name "Net-(Q3-C)") (class "Default")
      (node (ref "Q3") (pin "2") (pinfunction "C_2") (pintype "passive"))
      (node (ref "RL3") (pin "4") (pinfunction "4_4") (pintype "passive"))
    )
    (net (code "51") (name "Net-(Q4-B)") (class "Default")
      (node (ref "Q4") (pin "3") (pinfunction "B_3") (pintype "passive"))
      (node (ref "R10") (pin "2") (pinfunction "2_2") (pintype "passive"))
    )
    (net (code "52") (name "Net-(Q4-C)") (class "Default")
      (node (ref "Q4") (pin "2") (pinfunction "C_2") (pintype "passive"))
      (node (ref "RL4") (pin "4") (pinfunction "4_4") (pintype "passive"))
    )
    (net (code "53") (name "Net-(Q5-B)") (class "Default")
      (node (ref "Q5") (pin "3") (pinfunction "B_3") (pintype "passive"))
      (node (ref "R24") (pin "2") (pinfunction "2_2") (pintype "passive"))
    )
    (net (code "54") (name "Net-(Q5-C)") (class "Default")
      (node (ref "Q5") (pin "2") (pinfunction "C_2") (pintype "passive"))
      (node (ref "RL5") (pin "4") (pinfunction "4_4") (pintype "passive"))
    )
    (net (code "55") (name "Net-(Q6-B)") (class "Default")
      (node (ref "Q6") (pin "3") (pinfunction "B_3") (pintype "passive"))
      (node (ref "R25") (pin "2") (pinfunction "2_2") (pintype "passive"))
    )
    (net (code "56") (name "Net-(Q6-C)") (class "Default")
      (node (ref "Q6") (pin "2") (pinfunction "C_2") (pintype "passive"))
      (node (ref "RL6") (pin "4") (pinfunction "4_4") (pintype "passive"))
    )
    (net (code "57") (name "Net-(Q7-B)") (class "Default")
      (node (ref "Q7") (pin "3") (pinfunction "B_3") (pintype "passive"))
      (node (ref "R26") (pin "2") (pinfunction "2_2") (pintype "passive"))
    )
    (net (code "58") (name "Net-(Q7-C)") (class "Default")
      (node (ref "Q7") (pin "2") (pinfunction "C_2") (pintype "passive"))
      (node (ref "RL7") (pin "4") (pinfunction "4_4") (pintype "passive"))
    )
    (net (code "59") (name "Net-(Q8-B)") (class "Default")
      (node (ref "Q8") (pin "3") (pinfunction "B_3") (pintype "passive"))
      (node (ref "R27") (pin "2") (pinfunction "2_2") (pintype "passive"))
    )
    (net (code "60") (name "Net-(Q8-C)") (class "Default")
      (node (ref "Q8") (pin "2") (pinfunction "C_2") (pintype "passive"))
      (node (ref "RL8") (pin "4") (pinfunction "4_4") (pintype "passive"))
    )
    (net (code "61") (name "Net-(R3-Pad1)") (class "Default")
      (node (ref "R3") (pin "1") (pinfunction "1_1") (pintype "passive"))
      (node (ref "RL1") (pin "5") (pinfunction "5_5") (pintype "passive"))
    )
    (net (code "62") (name "Net-(R4-Pad1)") (class "Default")
      (node (ref "R4") (pin "1") (pinfunction "1_1") (pintype "passive"))
      (node (ref "RL2") (pin "5") (pinfunction "5_5") (pintype "passive"))
    )
    (net (code "63") (name "Net-(R5-Pad1)") (class "Default")
      (node (ref "R5") (pin "1") (pinfunction "1_1") (pintype "passive"))
      (node (ref "RL3") (pin "5") (pinfunction "5_5") (pintype "passive"))
    )
    (net (code "64") (name "Net-(R6-Pad1)") (class "Default")
      (node (ref "R6") (pin "1") (pinfunction "1_1") (pintype "passive"))
      (node (ref "RL4") (pin "5") (pinfunction "5_5") (pintype "passive"))
    )
    (net (code "65") (name "Net-(R16-Pad1)") (class "Default")
      (node (ref "R16") (pin "1") (pinfunction "1_1") (pintype "passive"))
      (node (ref "RL5") (pin "5") (pinfunction "5_5") (pintype "passive"))
    )
    (net (code "66") (name "Net-(R17-Pad1)") (class "Default")
      (node (ref "R17") (pin "1") (pinfunction "1_1") (pintype "passive"))
      (node (ref "RL6") (pin "5") (pinfunction "5_5") (pintype "passive"))
    )
    (net (code "67") (name "Net-(R18-Pad1)") (class "Default")
      (node (ref "R18") (pin "1") (pinfunction "1_1") (pintype "passive"))
      (node (ref "RL7") (pin "5") (pinfunction "5_5") (pintype "passive"))
    )
    (net (code "68") (name "Net-(R19-Pad1)") (class "Default")
      (node (ref "R19") (pin "1") (pinfunction "1_1") (pintype "passive"))
      (node (ref "RL8") (pin "5") (pinfunction "5_5") (pintype "passive"))
    )
    (net (code "69") (name "unconnected-(J9-Pad4)") (class "Default")
      (node (ref "J9") (pin "4") (pinfunction "4_4") (pintype "passive"))
    )
    (net (code "70") (name "unconnected-(J9-SHIELD-PadS1)") (class "Default")
      (node (ref "J9") (pin "S1") (pinfunction "SHIELD_S1") (pintype "passive"))
    )
    (net (code "71") (name "unconnected-(J9-SHIELD-PadS2)") (class "Default")
      (node (ref "J9") (pin "S2") (pinfunction "SHIELD_S2") (pintype "passive"))
    )
    (net (code "72") (name "unconnected-(J9-SHIELD-PadS3)") (class "Default")
      (node (ref "J9") (pin "S3") (pinfunction "SHIELD_S3") (pintype "passive"))
    )
    (net (code "73") (name "unconnected-(J9-SHIELD-PadS4)") (class "Default")
      (node (ref "J9") (pin "S4") (pinfunction "SHIELD_S4") (pintype "passive"))
    )
    (net (code "74") (name "unconnected-(J9-SHIELD-PadS5)") (class "Default")
      (node (ref "J9") (pin "S5") (pinfunction "SHIELD_S5") (pintype "passive"))
    )
    (net (code "75") (name "unconnected-(J9-SHIELD-PadS6)") (class "Default")
      (node (ref "J9") (pin "S6") (pinfunction "SHIELD_S6") (pintype "passive"))
    )
    (net (code "76") (name "unconnected-(M1-CLK-Pad20)") (class "Default")
      (node (ref "M1") (pin "20") (pinfunction "CLK_20") (pintype "passive"))
    )
    (net (code "77") (name "unconnected-(M1-CMD-Pad19)") (class "Default")
      (node (ref "M1") (pin "19") (pinfunction "CMD_19") (pintype "passive"))
    )
    (net (code "78") (name "unconnected-(M1-IO2-Pad24)") (class "Default")
      (node (ref "M1") (pin "24") (pinfunction "IO2_24") (pintype "passive"))
    )
    (net (code "79") (name "unconnected-(M1-IO12-Pad14)") (class "Default")
      (node (ref "M1") (pin "14") (pinfunction "IO12_14") (pintype "passive"))
    )
    (net (code "80") (name "unconnected-(M1-IO15-Pad23)") (class "Default")
      (node (ref "M1") (pin "23") (pinfunction "IO15_23") (pintype "passive"))
    )
    (net (code "81") (name "unconnected-(M1-IO35-Pad7)") (class "Default")
      (node (ref "M1") (pin "7") (pinfunction "IO35_7") (pintype "passive"))
    )
    (net (code "82") (name "unconnected-(M1-NC-Pad32)") (class "Default")
      (node (ref "M1") (pin "32") (pinfunction "NC_32") (pintype "passive"))
    )
    (net (code "83") (name "unconnected-(M1-SD0-Pad21)") (class "Default")
      (node (ref "M1") (pin "21") (pinfunction "SD0_21") (pintype "passive"))
    )
    (net (code "84") (name "unconnected-(M1-SD1-Pad22)") (class "Default")
      (node (ref "M1") (pin "22") (pinfunction "SD1_22") (pintype "passive"))
    )
    (net (code "85") (name "unconnected-(M1-SD2-Pad17)") (class "Default")
      (node (ref "M1") (pin "17") (pinfunction "SD2_17") (pintype "passive"))
    )
    (net (code "86") (name "unconnected-(M1-SD3-Pad18)") (class "Default")
      (node (ref "M1") (pin "18") (pinfunction "SD3_18") (pintype "passive"))
    )
    (net (code "87") (name "unconnected-(M1-SENSOR_VN-Pad5)") (class "Default")
      (node (ref "M1") (pin "5") (pinfunction "SENSOR_VN_5") (pintype "passive"))
    )
    (net (code "88") (name "unconnected-(M1-SENSOR_VP-Pad4)") (class "Default")
      (node (ref "M1") (pin "4") (pinfunction "SENSOR_VP_4") (pintype "passive"))
    )
    (net (code "89") (name "unconnected-(RL1-Pad2)") (class "Default")
      (node (ref "RL1") (pin "2") (pinfunction "2_2") (pintype "passive"))
    )
    (net (code "90") (name "unconnected-(RL2-Pad2)") (class "Default")
      (node (ref "RL2") (pin "2") (pinfunction "2_2") (pintype "passive"))
    )
    (net (code "91") (name "unconnected-(RL3-Pad2)") (class "Default")
      (node (ref "RL3") (pin "2") (pinfunction "2_2") (pintype "passive"))
    )
    (net (code "92") (name "unconnected-(RL4-Pad2)") (class "Default")
      (node (ref "RL4") (pin "2") (pinfunction "2_2") (pintype "passive"))
    )
    (net (code "93") (name "unconnected-(RL5-Pad2)") (class "Default")
      (node (ref "RL5") (pin "2") (pinfunction "2_2") (pintype "passive"))
    )
    (net (code "94") (name "unconnected-(RL6-Pad2)") (class "Default")
      (node (ref "RL6") (pin "2") (pinfunction "2_2") (pintype "passive"))
    )
    (net (code "95") (name "unconnected-(RL7-Pad2)") (class "Default")
      (node (ref "RL7") (pin "2") (pinfunction "2_2") (pintype "passive"))
    )
    (net (code "96") (name "unconnected-(RL8-Pad2)") (class "Default")
      (node (ref "RL8") (pin "2") (pinfunction "2_2") (pintype "passive"))
    )
  )
)
